# FAN_CTRL.net
KiCad netlist of a schematic drawn in Altium Designer
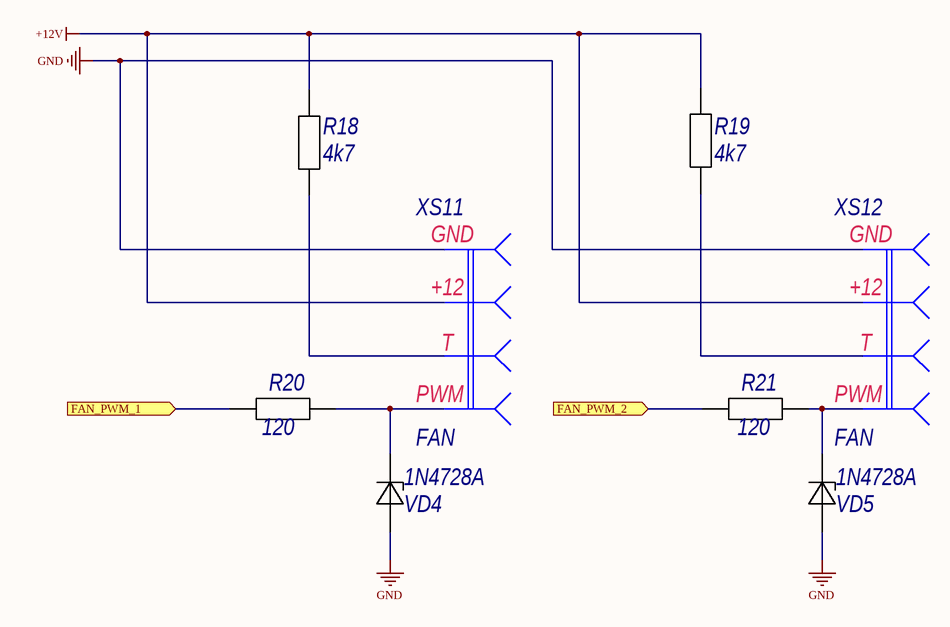
[diagram p0: FAN_CTRL.SchDoc]

(export (version "E")
  (design (tool "Eeschema 10.0.6"))
  (components
    (comp (ref "R18")
      (value "4k7")
      (footprint "C0805R")
      (fields (field (name "PUBLISHER") "Andrew Danich"))
      (libsource (lib "PA_control_board") (part "RES_0805"))
    )
    (comp (ref "R19")
      (value "4k7")
      (footprint "C0805R")
      (fields (field (name "PUBLISHER") "Andrew Danich"))
      (libsource (lib "PA_control_board") (part "RES_0805"))
    )
    (comp (ref "R20")
      (value "120")
      (footprint "C0805R")
      (fields (field (name "PUBLISHER") "Andrew Danich"))
      (libsource (lib "PA_control_board") (part "RES_0805"))
    )
    (comp (ref "R21")
      (value "120")
      (footprint "C0805R")
      (fields (field (name "PUBLISHER") "Andrew Danich"))
      (libsource (lib "PA_control_board") (part "RES_0805"))
    )
    (comp (ref "VD4")
      (value "1N4728A")
      (footprint "DO-41")
      (fields (field (name "PUBLISHER") "Andrew Danich"))
      (libsource (lib "PA_control_board") (part "1N4728A"))
    )
    (comp (ref "VD5")
      (value "1N4728A")
      (footprint "DO-41")
      (fields (field (name "PUBLISHER") "Andrew Danich"))
      (libsource (lib "PA_control_board") (part "1N4728A"))
    )
    (comp (ref "XS11")
      (value "FAN")
      (footprint "PLD1X4")
      (fields (field (name "PUBLISHER") "Andrew Danich"))
      (libsource (lib "PA_control_board") (part "FAN_CON"))
    )
    (comp (ref "XS12")
      (value "FAN")
      (footprint "PLD1X4")
      (fields (field (name "PUBLISHER") "Andrew Danich"))
      (libsource (lib "PA_control_board") (part "FAN_CON"))
    )
  )
  (nets
    (net (code "1") (name "+12V") (class "Default")
      (node (ref "R18") (pin "2") (pinfunction "2_2") (pintype "passive"))
      (node (ref "R19") (pin "2") (pinfunction "2_2") (pintype "passive"))
      (node (ref "XS11") (pin "2") (pintype "passive"))
      (node (ref "XS12") (pin "2") (pintype "passive"))
    )
    (net (code "2") (name "/FAN_PWM_1") (class "Default")
      (node (ref "R20") (pin "1") (pinfunction "1_1") (pintype "passive"))
    )
    (net (code "3") (name "/FAN_PWM_2") (class "Default")
      (node (ref "R21") (pin "1") (pinfunction "1_1") (pintype "passive"))
    )
    (net (code "4") (name "GND") (class "Default")
      (node (ref "VD4") (pin "1") (pinfunction "А_1") (pintype "passive"))
      (node (ref "VD5") (pin "1") (pinfunction "А_1") (pintype "passive"))
      (node (ref "XS11") (pin "1") (pintype "passive"))
      (node (ref "XS12") (pin "1") (pintype "passive"))
    )
    (net (code "5") (name "Net-(R18-Pad1)") (class "Default")
      (node (ref "R18") (pin "1") (pinfunction "1_1") (pintype "passive"))
      (node (ref "XS11") (pin "3") (pintype "passive"))
    )
    (net (code "6") (name "Net-(R19-Pad1)") (class "Default")
      (node (ref "R19") (pin "1") (pinfunction "1_1") (pintype "passive"))
      (node (ref "XS12") (pin "3") (pintype "passive"))
    )
    (net (code "7") (name "Net-(VD4-К)") (class "Default")
      (node (ref "R20") (pin "2") (pinfunction "2_2") (pintype "passive"))
      (node (ref "VD4") (pin "2") (pinfunction "К_2") (pintype "passive"))
      (node (ref "XS11") (pin "4") (pintype "passive"))
    )
    (net (code "8") (name "Net-(VD5-К)") (class "Default")
      (node (ref "R21") (pin "2") (pinfunction "2_2") (pintype "passive"))
      (node (ref "VD5") (pin "2") (pinfunction "К_2") (pintype "passive"))
      (node (ref "XS12") (pin "4") (pintype "passive"))
    )
  )
)
